# Encoder_Baord.net
KiCad netlist of a schematic drawn in Altium Designer
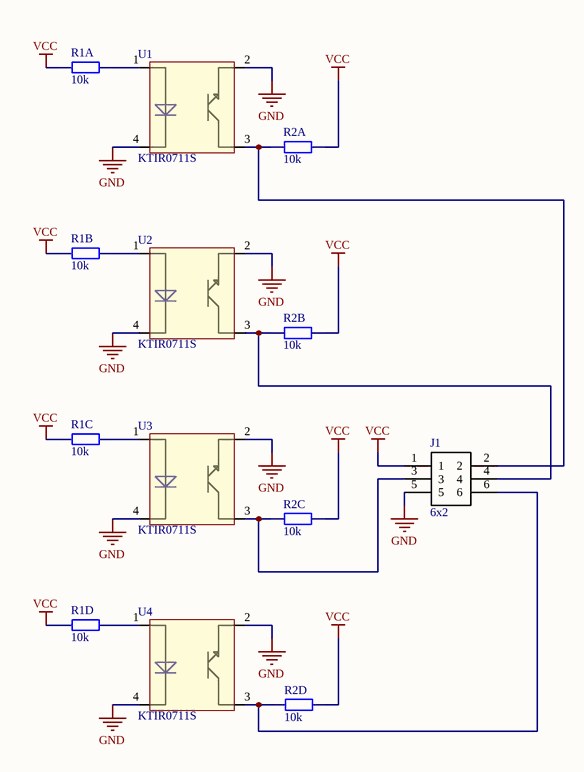
[diagram p0: Encoder_Baord.SchDoc]

(export (version "E")
  (design (tool "Eeschema 10.0.6"))
  (components
    (comp (ref "J1")
      (value "6x2")
      (footprint "Goldpin 2.00mm pin 2X3 angle")
      (description "Goldpin 2mmm angle")
      (libsource (lib "rys_component_lib") (part "Header 2mm 6-way"))
    )
    (comp (ref "R1")
      (value "10k")
      (footprint "Other-Discrete:1206_4R")
      (description "Resistor Pack, Multi part")
      (libsource (lib "Disc-Other") (part "R_4R_MP"))
    )
    (comp (ref "R2")
      (value "10k")
      (footprint "Other-Discrete:1206_4R")
      (description "Resistor Pack, Multi part")
      (libsource (lib "Disc-Other") (part "R_4R_MP"))
    )
    (comp (ref "U1")
      (value "KTIR0711S")
      (footprint "KTIR0711S")
      (description "KTIR0711S photointerrupter")
      (libsource (lib "rys_component_lib") (part "KTIR0711S"))
    )
    (comp (ref "U2")
      (value "KTIR0711S")
      (footprint "KTIR0711S")
      (description "KTIR0711S photointerrupter")
      (libsource (lib "rys_component_lib") (part "KTIR0711S"))
    )
    (comp (ref "U3")
      (value "KTIR0711S")
      (footprint "KTIR0711S")
      (description "KTIR0711S photointerrupter")
      (libsource (lib "rys_component_lib") (part "KTIR0711S"))
    )
    (comp (ref "U4")
      (value "KTIR0711S")
      (footprint "KTIR0711S")
      (description "KTIR0711S photointerrupter")
      (libsource (lib "rys_component_lib") (part "KTIR0711S"))
    )
  )
  (nets
    (net (code "1") (name "GND") (class "Default")
      (node (ref "J1") (pin "5") (pinfunction "5_5") (pintype "passive"))
      (node (ref "U1") (pin "2") (pinfunction "2_2") (pintype "passive"))
      (node (ref "U1") (pin "4") (pinfunction "4_4") (pintype "passive"))
      (node (ref "U2") (pin "2") (pinfunction "2_2") (pintype "passive"))
      (node (ref "U2") (pin "4") (pinfunction "4_4") (pintype "passive"))
      (node (ref "U3") (pin "2") (pinfunction "2_2") (pintype "passive"))
      (node (ref "U3") (pin "4") (pinfunction "4_4") (pintype "passive"))
      (node (ref "U4") (pin "2") (pinfunction "2_2") (pintype "passive"))
      (node (ref "U4") (pin "4") (pinfunction "4_4") (pintype "passive"))
    )
    (net (code "2") (name "Net-(J1-Pad2)") (class "Default")
      (node (ref "J1") (pin "2") (pinfunction "2_2") (pintype "passive"))
      (node (ref "R2") (pin "8") (pinfunction "8_8") (pintype "passive"))
      (node (ref "U1") (pin "3") (pinfunction "3_3") (pintype "passive"))
    )
    (net (code "3") (name "Net-(J1-Pad3)") (class "Default")
      (node (ref "J1") (pin "3") (pinfunction "3_3") (pintype "passive"))
      (node (ref "R2") (pin "6") (pinfunction "6_6") (pintype "passive"))
      (node (ref "U3") (pin "3") (pinfunction "3_3") (pintype "passive"))
    )
    (net (code "4") (name "Net-(J1-Pad4)") (class "Default")
      (node (ref "J1") (pin "4") (pinfunction "4_4") (pintype "passive"))
      (node (ref "R2") (pin "7") (pinfunction "7_7") (pintype "passive"))
      (node (ref "U2") (pin "3") (pinfunction "3_3") (pintype "passive"))
    )
    (net (code "5") (name "Net-(J1-Pad6)") (class "Default")
      (node (ref "J1") (pin "6") (pinfunction "6_6") (pintype "passive"))
      (node (ref "R2") (pin "5") (pinfunction "5_5") (pintype "passive"))
      (node (ref "U4") (pin "3") (pinfunction "3_3") (pintype "passive"))
    )
    (net (code "6") (name "Net-(R1-Pad5)") (class "Default")
      (node (ref "R1") (pin "5") (pinfunction "5_5") (pintype "passive"))
      (node (ref "U4") (pin "1") (pinfunction "1_1") (pintype "passive"))
    )
    (net (code "7") (name "Net-(R1-Pad6)") (class "Default")
      (node (ref "R1") (pin "6") (pinfunction "6_6") (pintype "passive"))
      (node (ref "U3") (pin "1") (pinfunction "1_1") (pintype "passive"))
    )
    (net (code "8") (name "Net-(R1-Pad7)") (class "Default")
      (node (ref "R1") (pin "7") (pinfunction "7_7") (pintype "passive"))
      (node (ref "U2") (pin "1") (pinfunction "1_1") (pintype "passive"))
    )
    (net (code "9") (name "Net-(R1-Pad8)") (class "Default")
      (node (ref "R1") (pin "8") (pinfunction "8_8") (pintype "passive"))
      (node (ref "U1") (pin "1") (pinfunction "1_1") (pintype "passive"))
    )
    (net (code "10") (name "VCC") (class "Default")
      (node (ref "J1") (pin "1") (pinfunction "1_1") (pintype "passive"))
      (node (ref "R1") (pin "1") (pinfunction "1_1") (pintype "passive"))
      (node (ref "R1") (pin "2") (pinfunction "2_2") (pintype "passive"))
      (node (ref "R1") (pin "3") (pinfunction "3_3") (pintype "passive"))
      (node (ref "R1") (pin "4") (pinfunction "4_4") (pintype "passive"))
      (node (ref "R2") (pin "1") (pinfunction "1_1") (pintype "passive"))
      (node (ref "R2") (pin "2") (pinfunction "2_2") (pintype "passive"))
      (node (ref "R2") (pin "3") (pinfunction "3_3") (pintype "passive"))
      (node (ref "R2") (pin "4") (pinfunction "4_4") (pintype "passive"))
    )
  )
)
